# 5V_LDO.net
KiCad netlist of a schematic drawn in Altium Designer
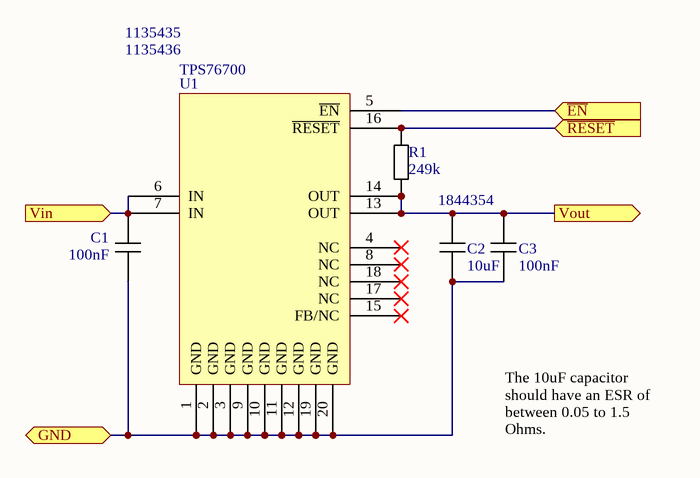
[diagram p0: 5V_LDO.SchDoc]

(export (version "E")
  (design (tool "Eeschema 10.0.6"))
  (components
    (comp (ref "C1")
      (value "100nF")
      (footprint "0805 Cap")
      (description "0805 MLCC - X7R, 10%")
      (fields (field (name "Comment") "0805 Cap"))
      (libsource (lib "Schlib1") (part "0805 MLCC - X7R, 10%"))
    )
    (comp (ref "C2")
      (value "10uF")
      (footprint "1210 Cap")
      (description "1210 MLCC - X7R, 10%")
      (fields (field (name "SUPPLIER PART NUMBER 1") "1844354") (field (name "Comment") "1210 Cap"))
      (libsource (lib "Schlib1") (part "1210 MLCC - X7R, 10%"))
    )
    (comp (ref "C3")
      (value "100nF")
      (footprint "0805 Cap")
      (description "0805 MLCC - X7R, 10%")
      (fields (field (name "Comment") "0805 Cap"))
      (libsource (lib "Schlib1") (part "0805 MLCC - X7R, 10%"))
    )
    (comp (ref "R1")
      (value "249k")
      (footprint "0805 Resistor")
      (description "0805 Thick Film Resistor 1%")
      (fields (field (name "Comment") "0805 Resistor"))
      (libsource (lib "Schlib1") (part "0805 Thick Film Resistor 1%"))
    )
    (comp (ref "U1")
      (value "TPS76700")
      (footprint "SOP-20 TPS76700")
      (description "LDO Regulator - ER")
      (fields
        (field (name "SUPPLIER PART NUMBER 1") "1135436")
        (field (name "SUPPLIER PART NUMBER 2") "1135435")
      )
      (libsource (lib "Schlib1") (part "TPS76700"))
    )
  )
  (nets
    (net (code "1") (name "/GND") (class "Default")
      (node (ref "C1") (pin "1") (pinfunction "1_1") (pintype "passive"))
      (node (ref "C2") (pin "1") (pinfunction "1_1") (pintype "passive"))
      (node (ref "C3") (pin "1") (pinfunction "1_1") (pintype "passive"))
      (node (ref "U1") (pin "1") (pinfunction "GND_1") (pintype "passive"))
      (node (ref "U1") (pin "10") (pinfunction "GND_10") (pintype "passive"))
      (node (ref "U1") (pin "11") (pinfunction "GND_11") (pintype "passive"))
      (node (ref "U1") (pin "12") (pinfunction "GND_12") (pintype "passive"))
      (node (ref "U1") (pin "19") (pinfunction "GND_19") (pintype "passive"))
      (node (ref "U1") (pin "2") (pinfunction "GND_2") (pintype "passive"))
      (node (ref "U1") (pin "20") (pinfunction "GND_20") (pintype "passive"))
      (node (ref "U1") (pin "3") (pinfunction "GND_3") (pintype "passive"))
      (node (ref "U1") (pin "9") (pinfunction "GND_9") (pintype "passive"))
    )
    (net (code "2") (name "/Vin") (class "Default")
      (node (ref "C1") (pin "2") (pinfunction "2_2") (pintype "passive"))
      (node (ref "U1") (pin "6") (pinfunction "IN_6") (pintype "passive"))
      (node (ref "U1") (pin "7") (pinfunction "IN_7") (pintype "passive"))
    )
    (net (code "3") (name "/Vout") (class "Default")
      (node (ref "C2") (pin "2") (pinfunction "2_2") (pintype "passive"))
      (node (ref "C3") (pin "2") (pinfunction "2_2") (pintype "passive"))
      (node (ref "R1") (pin "1") (pinfunction "1_1") (pintype "passive"))
      (node (ref "U1") (pin "13") (pinfunction "OUT_13") (pintype "passive"))
      (node (ref "U1") (pin "14") (pinfunction "OUT_14") (pintype "passive"))
    )
    (net (code "4") (name "/~{EN}") (class "Default")
      (node (ref "U1") (pin "5") (pinfunction "~{EN}_5") (pintype "passive"))
    )
    (net (code "5") (name "/~{RESET}") (class "Default")
      (node (ref "R1") (pin "2") (pinfunction "2_2") (pintype "passive"))
      (node (ref "U1") (pin "16") (pinfunction "~{RESET}_16") (pintype "passive"))
    )
    (net (code "6") (name "unconnected-(U1-FB{slash}NC-Pad15)") (class "Default")
      (node (ref "U1") (pin "15") (pinfunction "FB/NC_15") (pintype "passive+no_connect"))
    )
    (net (code "7") (name "unconnected-(U1-NC-Pad4)") (class "Default")
      (node (ref "U1") (pin "4") (pinfunction "NC_4") (pintype "passive+no_connect"))
    )
    (net (code "8") (name "unconnected-(U1-NC-Pad8)") (class "Default")
      (node (ref "U1") (pin "8") (pinfunction "NC_8") (pintype "passive+no_connect"))
    )
    (net (code "9") (name "unconnected-(U1-NC-Pad17)") (class "Default")
      (node (ref "U1") (pin "17") (pinfunction "NC_17") (pintype "passive+no_connect"))
    )
    (net (code "10") (name "unconnected-(U1-NC-Pad18)") (class "Default")
      (node (ref "U1") (pin "18") (pinfunction "NC_18") (pintype "passive+no_connect"))
    )
  )
)
